# InkTime_Schematic.net
KiCad netlist of a schematic drawn in EAGLE
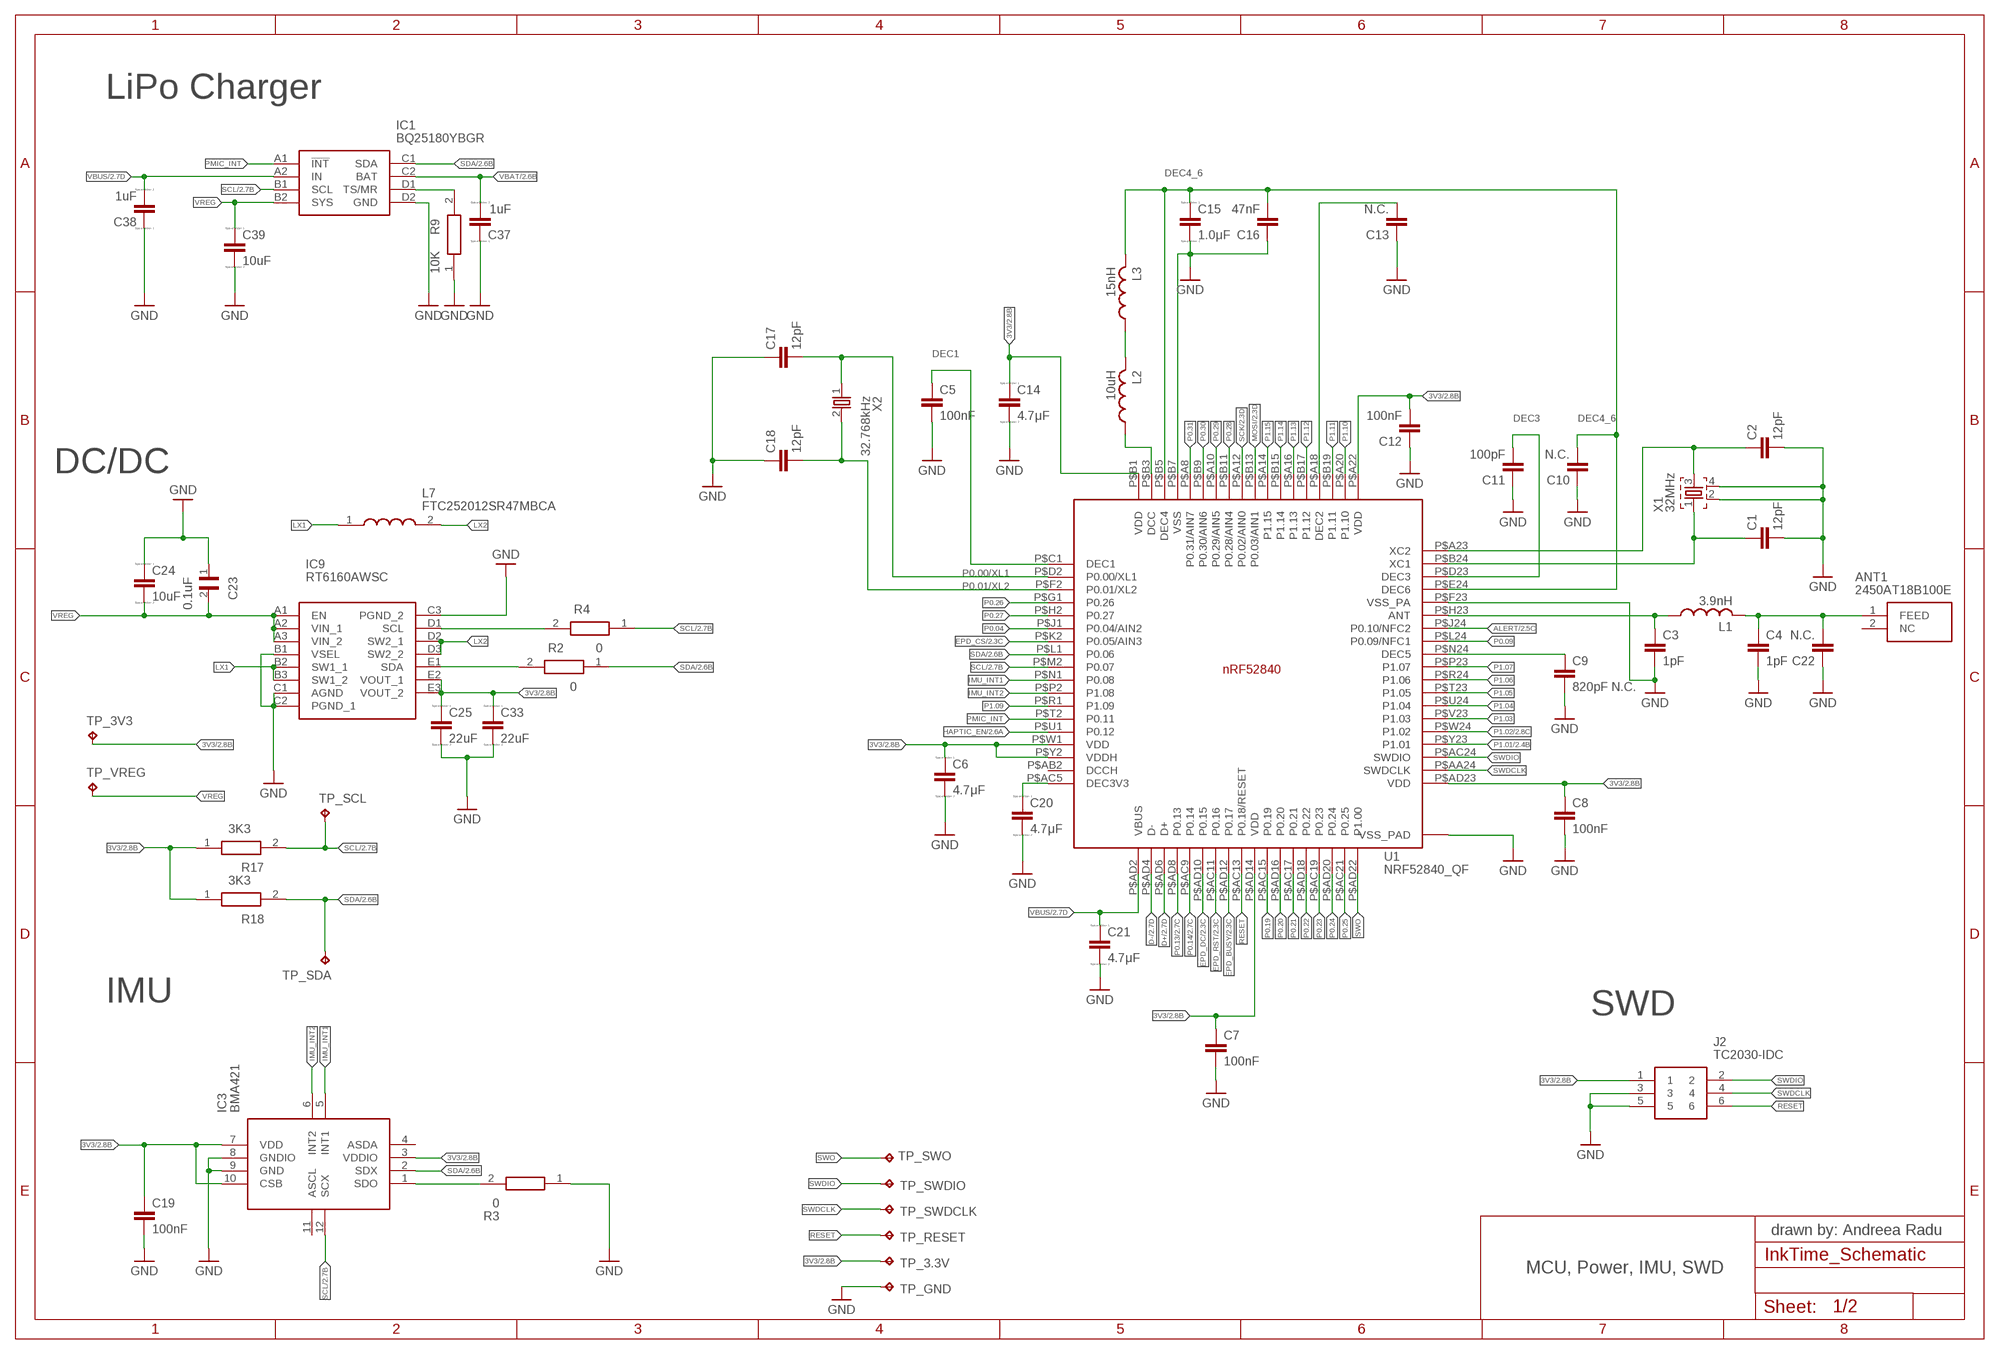
[diagram p0: schematic, sheet 1]
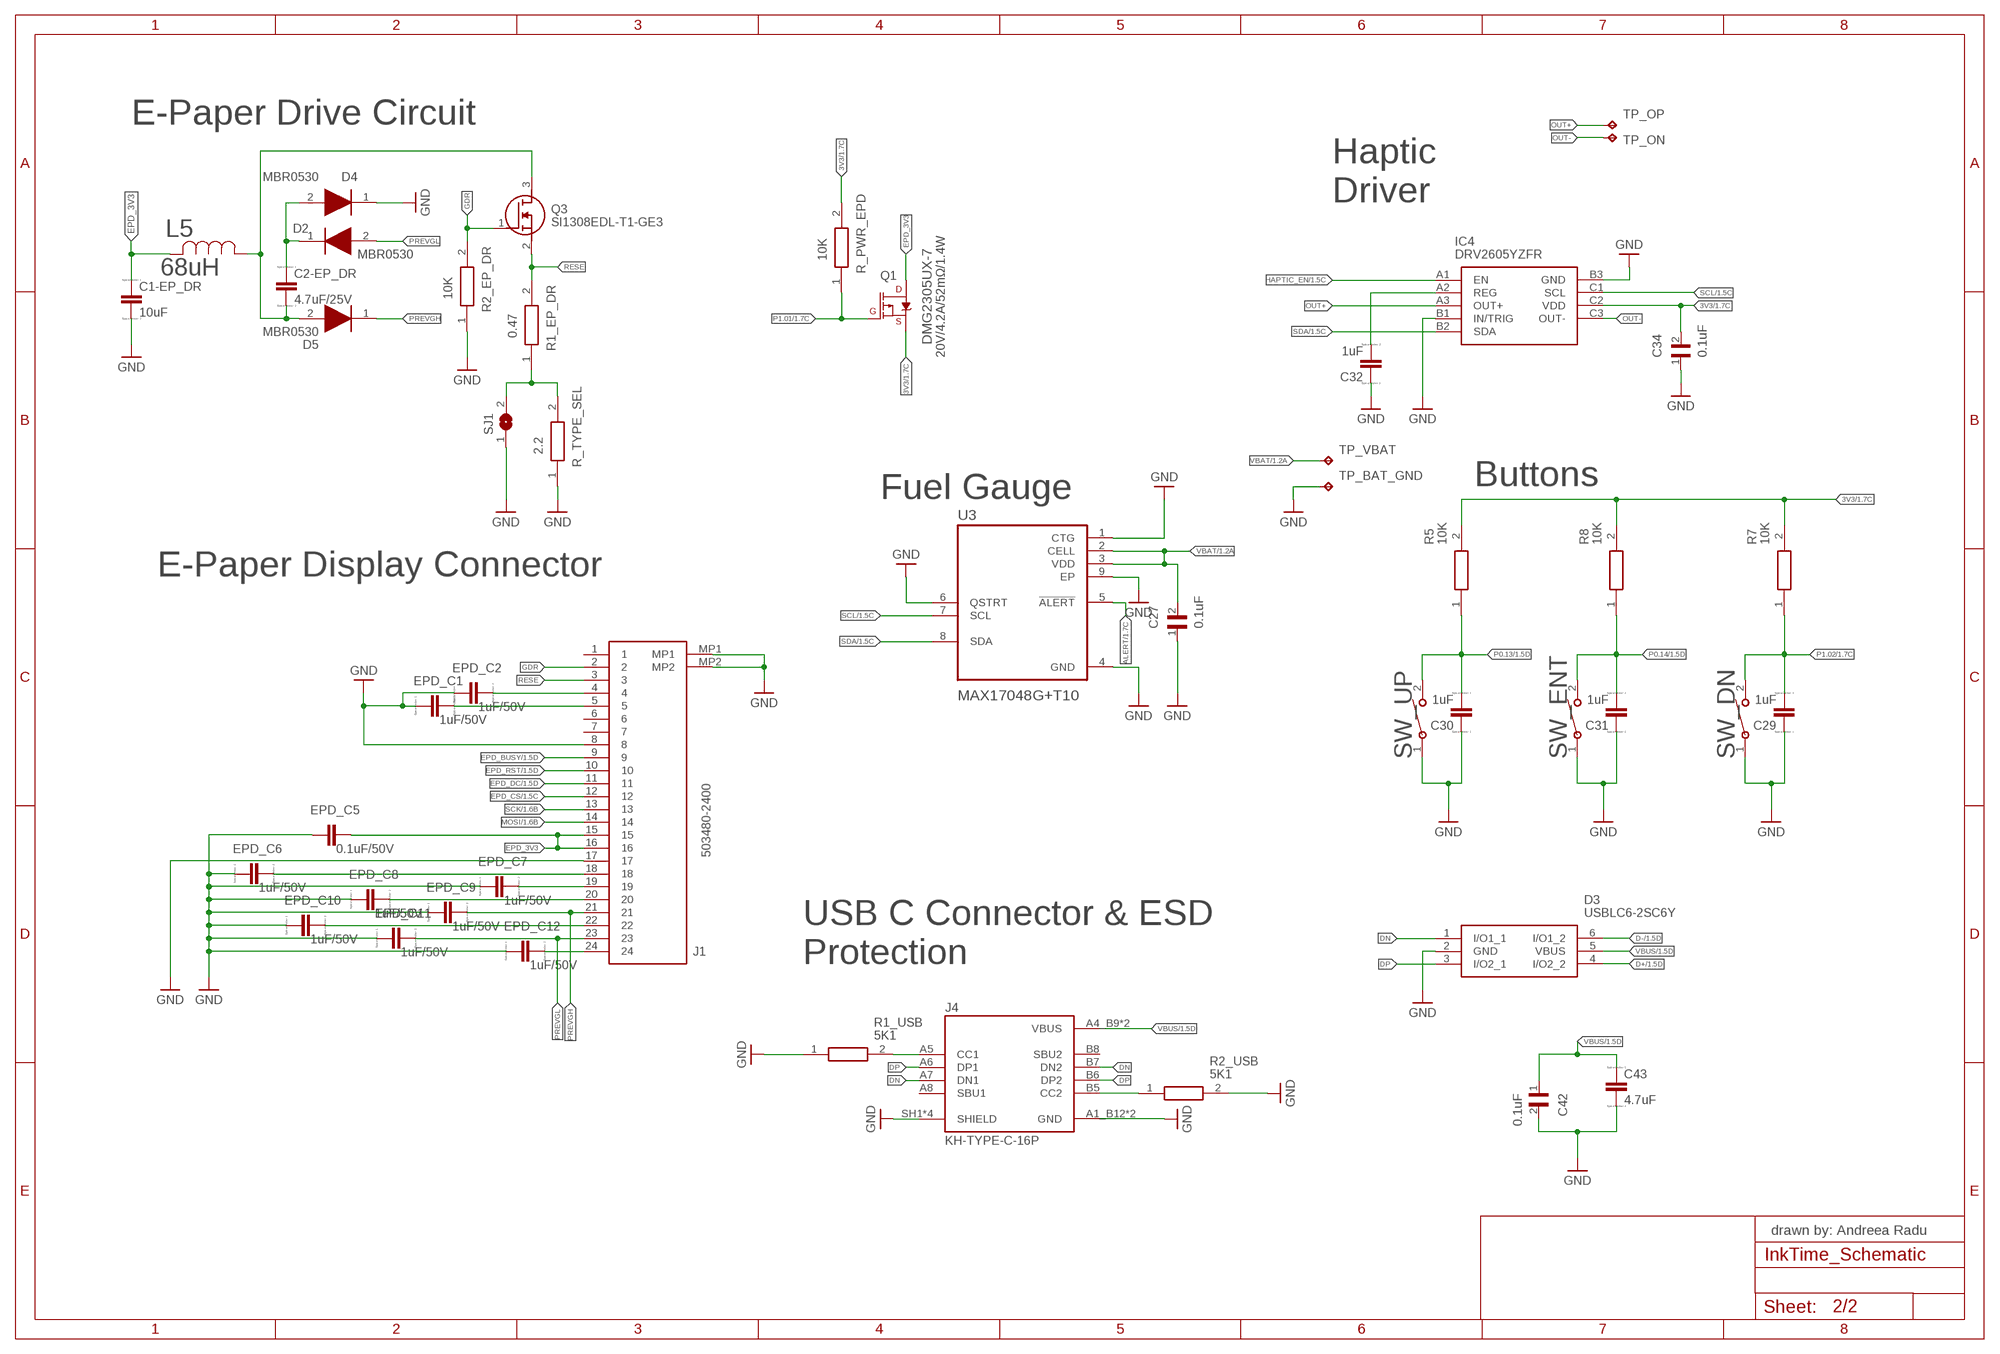
[diagram p1: schematic, sheet 2]

(export (version "E")
  (design (tool "Eeschema 10.0.6"))
  (components
    (comp (ref "ANT1")
      (value "2450AT18B100E")
      (footprint "eagle-import:2450AT18B100E_ANTC3216X140N")
      (fields (field (name "MOUSER_PART_NUMBER") "609-2450AT18B100E"))
      (libsource (lib "eagle-import") (part "2450AT18B100E_2450AT18B100E"))
    )
    (comp (ref "C1")
      (value "12pF")
      (footprint "eagle-import:NORDIC_NRF_3_RESC0201_L")
      (libsource (lib "eagle-import") (part "NORDIC_NRF_3_CAPACITOR_0201_L"))
    )
    (comp (ref "C2")
      (value "12pF")
      (footprint "eagle-import:NORDIC_NRF_3_RESC0201_L")
      (libsource (lib "eagle-import") (part "NORDIC_NRF_3_CAPACITOR_0201_L"))
    )
    (comp (ref "C3")
      (value "1pF")
      (footprint "eagle-import:NORDIC_NRF_3_RESC0201_L")
      (libsource (lib "eagle-import") (part "NORDIC_NRF_3_CAPACITOR_0201_L"))
    )
    (comp (ref "C4")
      (value "1pF")
      (footprint "eagle-import:NORDIC_NRF_3_RESC0201_L")
      (libsource (lib "eagle-import") (part "NORDIC_NRF_3_CAPACITOR_0201_L"))
    )
    (comp (ref "C5")
      (value "100nF")
      (footprint "eagle-import:NORDIC_NRF_3_RESC0201_L")
      (libsource (lib "eagle-import") (part "NORDIC_NRF_3_CAPACITOR_0201_L"))
    )
    (comp (ref "C6")
      (value "4.7μF")
      (footprint "eagle-import:ESP32_C6_LIBRARY_1_ESP32_WROVER_EAGLE-LTSPICE_C0402")
      (libsource (lib "eagle-import") (part "ESP32_C6_LIBRARY_1_ESP32_WROVER_EAGLE-LTSPICE_CC0402"))
    )
    (comp (ref "C7")
      (value "100nF")
      (footprint "eagle-import:NORDIC_NRF_3_RESC0201_L")
      (libsource (lib "eagle-import") (part "NORDIC_NRF_3_CAPACITOR_0201_L"))
    )
    (comp (ref "C8")
      (value "100nF")
      (footprint "eagle-import:NORDIC_NRF_3_RESC0201_L")
      (libsource (lib "eagle-import") (part "NORDIC_NRF_3_CAPACITOR_0201_L"))
    )
    (comp (ref "C9")
      (value "820pF N.C.")
      (footprint "eagle-import:NORDIC_NRF_3_RESC0201_L")
      (libsource (lib "eagle-import") (part "NORDIC_NRF_3_CAPACITOR_0201_L"))
    )
    (comp (ref "C10")
      (value "N.C.")
      (footprint "eagle-import:NORDIC_NRF_3_RESC0201_L")
      (libsource (lib "eagle-import") (part "NORDIC_NRF_3_CAPACITOR_0201_L"))
    )
    (comp (ref "C11")
      (value "100pF")
      (footprint "eagle-import:NORDIC_NRF_3_RESC0201_L")
      (libsource (lib "eagle-import") (part "NORDIC_NRF_3_CAPACITOR_0201_L"))
    )
    (comp (ref "C12")
      (value "100nF")
      (footprint "eagle-import:NORDIC_NRF_3_RESC0201_L")
      (libsource (lib "eagle-import") (part "NORDIC_NRF_3_CAPACITOR_0201_L"))
    )
    (comp (ref "C13")
      (value "N.C.")
      (footprint "eagle-import:NORDIC_NRF_3_RESC0201_L")
      (libsource (lib "eagle-import") (part "NORDIC_NRF_3_CAPACITOR_0201_L"))
    )
    (comp (ref "C14")
      (value "4.7μF")
      (footprint "eagle-import:ESP32_C6_LIBRARY_1_ESP32_WROVER_EAGLE-LTSPICE_C0402")
      (libsource (lib "eagle-import") (part "ESP32_C6_LIBRARY_1_ESP32_WROVER_EAGLE-LTSPICE_CC0402"))
    )
    (comp (ref "C15")
      (value "1.0μF")
      (footprint "eagle-import:ESP32_C6_LIBRARY_1_ESP32_WROVER_EAGLE-LTSPICE_C0402")
      (libsource (lib "eagle-import") (part "ESP32_C6_LIBRARY_1_ESP32_WROVER_EAGLE-LTSPICE_CC0402"))
    )
    (comp (ref "C16")
      (value "47nF")
      (footprint "eagle-import:NORDIC_NRF_3_RESC0201_L")
      (libsource (lib "eagle-import") (part "NORDIC_NRF_3_CAPACITOR_0201_L"))
    )
    (comp (ref "C17")
      (value "12pF")
      (footprint "eagle-import:NORDIC_NRF_3_RESC0201_L")
      (libsource (lib "eagle-import") (part "NORDIC_NRF_3_CAPACITOR_0201_L"))
    )
    (comp (ref "C18")
      (value "12pF")
      (footprint "eagle-import:NORDIC_NRF_3_RESC0201_L")
      (libsource (lib "eagle-import") (part "NORDIC_NRF_3_CAPACITOR_0201_L"))
    )
    (comp (ref "C19")
      (value "100nF")
      (footprint "eagle-import:NORDIC_NRF_3_RESC0201_L")
      (libsource (lib "eagle-import") (part "NORDIC_NRF_3_CAPACITOR_0201_L"))
    )
    (comp (ref "C20")
      (value "4.7μF")
      (footprint "eagle-import:ESP32_C6_LIBRARY_1_ESP32_WROVER_EAGLE-LTSPICE_C0402")
      (libsource (lib "eagle-import") (part "ESP32_C6_LIBRARY_1_ESP32_WROVER_EAGLE-LTSPICE_CC0402"))
    )
    (comp (ref "C21")
      (value "4.7μF")
      (footprint "eagle-import:ESP32_C6_LIBRARY_1_ESP32_WROVER_EAGLE-LTSPICE_C0402")
      (libsource (lib "eagle-import") (part "ESP32_C6_LIBRARY_1_ESP32_WROVER_EAGLE-LTSPICE_CC0402"))
    )
    (comp (ref "C22")
      (value "N.C.")
      (footprint "eagle-import:NORDIC_NRF_3_RESC0201_L")
      (libsource (lib "eagle-import") (part "NORDIC_NRF_3_CAPACITOR_0201_L"))
    )
    (comp (ref "C23")
      (value "0.1uF")
      (footprint "eagle-import:GRM011R60J152KE01L_2_CAPC0201X13N")
      (fields (field (name "MF") "Murata") (field (name "MP") "GRM011R60J152KE01L"))
      (libsource (lib "eagle-import") (part "GRM011R60J152KE01L_2_GRM011R60J152KE01L"))
    )
    (comp (ref "C24")
      (value "10uF")
      (footprint "eagle-import:ESP32_C6_LIBRARY_1_ESP32_WROVER_EAGLE-LTSPICE_C0402")
      (libsource (lib "eagle-import") (part "ESP32_C6_LIBRARY_1_ESP32_WROVER_EAGLE-LTSPICE_CC0402"))
    )
    (comp (ref "C25")
      (value "22uF")
      (footprint "eagle-import:ESP32_C6_LIBRARY_1_ESP32_WROVER_EAGLE-LTSPICE_C0402")
      (libsource (lib "eagle-import") (part "ESP32_C6_LIBRARY_1_ESP32_WROVER_EAGLE-LTSPICE_CC0402"))
    )
    (comp (ref "C33")
      (value "22uF")
      (footprint "eagle-import:ESP32_C6_LIBRARY_1_ESP32_WROVER_EAGLE-LTSPICE_C0402")
      (libsource (lib "eagle-import") (part "ESP32_C6_LIBRARY_1_ESP32_WROVER_EAGLE-LTSPICE_CC0402"))
    )
    (comp (ref "C37")
      (value "1uF")
      (footprint "eagle-import:ESP32_C6_LIBRARY_1_ESP32_WROVER_EAGLE-LTSPICE_C0402")
      (libsource (lib "eagle-import") (part "ESP32_C6_LIBRARY_1_ESP32_WROVER_EAGLE-LTSPICE_CC0402"))
    )
    (comp (ref "C38")
      (value "1uF")
      (footprint "eagle-import:ESP32_C6_LIBRARY_1_ESP32_WROVER_EAGLE-LTSPICE_C0402")
      (libsource (lib "eagle-import") (part "ESP32_C6_LIBRARY_1_ESP32_WROVER_EAGLE-LTSPICE_CC0402"))
    )
    (comp (ref "C39")
      (value "10uF")
      (footprint "eagle-import:ESP32_C6_LIBRARY_1_ESP32_WROVER_EAGLE-LTSPICE_C0402")
      (libsource (lib "eagle-import") (part "ESP32_C6_LIBRARY_1_ESP32_WROVER_EAGLE-LTSPICE_CC0402"))
    )
    (comp (ref "IC1")
      (value "BQ25180YBGR")
      (footprint "eagle-import:BQ25180YBGR_BGA8C40P2X4_100X155X50")
      (fields (field (name "MOUSER_PART_NUMBER") "595-BQ25180YBGR"))
      (libsource (lib "eagle-import") (part "BQ25180YBGR_BQ25180YBGR"))
    )
    (comp (ref "IC3")
      (value "BMA421")
      (footprint "eagle-import:BMA423_BMA423")
      (fields (field (name "ARROW_PART_NUMBER") "BMA423") (field (name "MOUSER_PART_NUMBER") "262-BMA423"))
      (libsource (lib "eagle-import") (part "BMA423_BMA423"))
    )
    (comp (ref "IC9")
      (value "RT6160AWSC")
      (footprint "eagle-import:RT6160AWSC_BGA15C40P3X5_140X230X60")
      (fields (field (name "MOUSER_PART_NUMBER") "835-RT6160AWSC"))
      (libsource (lib "eagle-import") (part "RT6160AWSC_RT6160AWSC"))
    )
    (comp (ref "J2")
      (value "TC2030-IDC")
      (footprint "eagle-import:TC2030-IDC_TC2030IDC")
      (libsource (lib "eagle-import") (part "TC2030-IDC_TC2030-IDC"))
    )
    (comp (ref "L1")
      (value "3.9nH")
      (footprint "eagle-import:NORDIC_NRF_2_RESC0402_L")
      (libsource (lib "eagle-import") (part "NORDIC_NRF_2_INDUCTOR_0402_L"))
    )
    (comp (ref "L2")
      (value "10uH")
      (footprint "eagle-import:NORDIC_NRF_2_RESC0402_L")
      (libsource (lib "eagle-import") (part "NORDIC_NRF_2_INDUCTOR_0402_L"))
    )
    (comp (ref "L3")
      (value "15nH")
      (footprint "eagle-import:NORDIC_NRF_2_RESC0402_L")
      (libsource (lib "eagle-import") (part "NORDIC_NRF_2_INDUCTOR_0402_L"))
    )
    (comp (ref "L7")
      (value "FTC252012SR47MBCA")
      (footprint "eagle-import:MLP2016SR47MT0S1_INDC2016X100N")
      (libsource (lib "eagle-import") (part "MLP2016SR47MT0S1_FTC252012SR47MBCA"))
    )
    (comp (ref "R2")
      (value "0")
      (footprint "eagle-import:CPF0201D7K68C1_0201")
      (libsource (lib "eagle-import") (part "CPF0201D7K68C1_CPF0201D7K68C1"))
    )
    (comp (ref "R3")
      (value "0")
      (footprint "eagle-import:CPF0201D7K68C1_0201")
      (libsource (lib "eagle-import") (part "CPF0201D7K68C1_CPF0201D7K68C1"))
    )
    (comp (ref "R4")
      (value "0")
      (footprint "eagle-import:CPF0201D7K68C1_0201")
      (libsource (lib "eagle-import") (part "CPF0201D7K68C1_CPF0201D7K68C1"))
    )
    (comp (ref "R9")
      (value "10K")
      (footprint "eagle-import:CPF0201D7K68C1_0201")
      (libsource (lib "eagle-import") (part "CPF0201D7K68C1_CPF0201D7K68C1"))
    )
    (comp (ref "R17")
      (value "3K3")
      (footprint "eagle-import:CPF0201D7K68C1_0201")
      (libsource (lib "eagle-import") (part "CPF0201D7K68C1_CPF0201D7K68C1"))
    )
    (comp (ref "R18")
      (value "3K3")
      (footprint "eagle-import:CPF0201D7K68C1_0201")
      (libsource (lib "eagle-import") (part "CPF0201D7K68C1_CPF0201D7K68C1"))
    )
    (comp (ref "TP_3.3V")
      (value "HECTOR_WATCH_1_TPTP20R")
      (footprint "eagle-import:HECTOR_WATCH_1_TP20R")
      (libsource (lib "eagle-import") (part "HECTOR_WATCH_1_TPTP20R"))
    )
    (comp (ref "TP_3V3")
      (value "HECTOR_WATCH_1_TPTP20R")
      (footprint "eagle-import:HECTOR_WATCH_1_TP20R")
      (libsource (lib "eagle-import") (part "HECTOR_WATCH_1_TPTP20R"))
    )
    (comp (ref "TP_GND")
      (value "HECTOR_WATCH_1_TPTP20R")
      (footprint "eagle-import:HECTOR_WATCH_1_TP20R")
      (libsource (lib "eagle-import") (part "HECTOR_WATCH_1_TPTP20R"))
    )
    (comp (ref "TP_RESET")
      (value "HECTOR_WATCH_1_TPTP20R")
      (footprint "eagle-import:HECTOR_WATCH_1_TP20R")
      (libsource (lib "eagle-import") (part "HECTOR_WATCH_1_TPTP20R"))
    )
    (comp (ref "TP_SCL")
      (value "HECTOR_WATCH_1_TPTP20R")
      (footprint "eagle-import:HECTOR_WATCH_1_TP20R")
      (libsource (lib "eagle-import") (part "HECTOR_WATCH_1_TPTP20R"))
    )
    (comp (ref "TP_SDA")
      (value "HECTOR_WATCH_1_TPTP20R")
      (footprint "eagle-import:HECTOR_WATCH_1_TP20R")
      (libsource (lib "eagle-import") (part "HECTOR_WATCH_1_TPTP20R"))
    )
    (comp (ref "TP_SWDCLK")
      (value "HECTOR_WATCH_1_TPTP20R")
      (footprint "eagle-import:HECTOR_WATCH_1_TP20R")
      (libsource (lib "eagle-import") (part "HECTOR_WATCH_1_TPTP20R"))
    )
    (comp (ref "TP_SWDIO")
      (value "HECTOR_WATCH_1_TPTP20R")
      (footprint "eagle-import:HECTOR_WATCH_1_TP20R")
      (libsource (lib "eagle-import") (part "HECTOR_WATCH_1_TPTP20R"))
    )
    (comp (ref "TP_SWO")
      (value "HECTOR_WATCH_1_TPTP20R")
      (footprint "eagle-import:HECTOR_WATCH_1_TP20R")
      (libsource (lib "eagle-import") (part "HECTOR_WATCH_1_TPTP20R"))
    )
    (comp (ref "TP_VREG")
      (value "HECTOR_WATCH_1_TPTP20R")
      (footprint "eagle-import:HECTOR_WATCH_1_TP20R")
      (libsource (lib "eagle-import") (part "HECTOR_WATCH_1_TPTP20R"))
    )
    (comp (ref "U1")
      (value "NRF52840_QF")
      (footprint "eagle-import:NORDIC_NRF_4_AQFN50P700X700X85_HS-74N")
      (libsource (lib "eagle-import") (part "NORDIC_NRF_4_NRF52840_QF"))
    )
    (comp (ref "X1")
      (value "32MHz")
      (footprint "eagle-import:NORDIC_NRF_BT-XTAL_2016_N")
      (libsource (lib "eagle-import") (part "NORDIC_NRF_XTAL_32MHZ"))
    )
    (comp (ref "X2")
      (value "32.768kHz")
      (footprint "eagle-import:NORDIC_NRF_1_XTAL_3215_N")
      (libsource (lib "eagle-import") (part "NORDIC_NRF_1_XTAL_32KHZ"))
    )
    (comp (ref "C1-EP_DR")
      (value "10uF")
      (footprint "eagle-import:ESP32_C6_LIBRARY_1_ESP32_WROVER_EAGLE-LTSPICE_C0402")
      (libsource (lib "eagle-import") (part "ESP32_C6_LIBRARY_1_ESP32_WROVER_EAGLE-LTSPICE_CC0402"))
    )
    (comp (ref "C2-EP_DR")
      (value "4.7uF/25V")
      (footprint "eagle-import:ESP32_C6_LIBRARY_1_ESP32_WROVER_EAGLE-LTSPICE_C0402")
      (libsource (lib "eagle-import") (part "ESP32_C6_LIBRARY_1_ESP32_WROVER_EAGLE-LTSPICE_CC0402"))
    )
    (comp (ref "C27")
      (value "0.1uF")
      (footprint "eagle-import:GRM011R60J152KE01L_2_CAPC0201X13N")
      (fields (field (name "MF") "Murata") (field (name "MP") "GRM011R60J152KE01L"))
      (libsource (lib "eagle-import") (part "GRM011R60J152KE01L_2_GRM011R60J152KE01L"))
    )
    (comp (ref "C29")
      (value "1uF")
      (footprint "eagle-import:ESP32_C6_LIBRARY_1_ESP32_WROVER_EAGLE-LTSPICE_C0402")
      (libsource (lib "eagle-import") (part "ESP32_C6_LIBRARY_1_ESP32_WROVER_EAGLE-LTSPICE_CC0402"))
    )
    (comp (ref "C30")
      (value "1uF")
      (footprint "eagle-import:ESP32_C6_LIBRARY_1_ESP32_WROVER_EAGLE-LTSPICE_C0402")
      (libsource (lib "eagle-import") (part "ESP32_C6_LIBRARY_1_ESP32_WROVER_EAGLE-LTSPICE_CC0402"))
    )
    (comp (ref "C31")
      (value "1uF")
      (footprint "eagle-import:ESP32_C6_LIBRARY_1_ESP32_WROVER_EAGLE-LTSPICE_C0402")
      (libsource (lib "eagle-import") (part "ESP32_C6_LIBRARY_1_ESP32_WROVER_EAGLE-LTSPICE_CC0402"))
    )
    (comp (ref "C32")
      (value "1uF")
      (footprint "eagle-import:ESP32_C6_LIBRARY_1_ESP32_WROVER_EAGLE-LTSPICE_C0402")
      (libsource (lib "eagle-import") (part "ESP32_C6_LIBRARY_1_ESP32_WROVER_EAGLE-LTSPICE_CC0402"))
    )
    (comp (ref "C34")
      (value "0.1uF")
      (footprint "eagle-import:GRM011R60J152KE01L_2_CAPC0201X13N")
      (fields (field (name "MF") "Murata") (field (name "MP") "GRM011R60J152KE01L"))
      (libsource (lib "eagle-import") (part "GRM011R60J152KE01L_2_GRM011R60J152KE01L"))
    )
    (comp (ref "C42")
      (value "0.1uF")
      (footprint "eagle-import:GRM011R60J152KE01L_2_CAPC0201X13N")
      (fields (field (name "MF") "Murata") (field (name "MP") "GRM011R60J152KE01L"))
      (libsource (lib "eagle-import") (part "GRM011R60J152KE01L_2_GRM011R60J152KE01L"))
    )
    (comp (ref "C43")
      (value "4.7uF")
      (footprint "eagle-import:ESP32_C6_LIBRARY_1_ESP32_WROVER_EAGLE-LTSPICE_C0402")
      (libsource (lib "eagle-import") (part "ESP32_C6_LIBRARY_1_ESP32_WROVER_EAGLE-LTSPICE_CC0402"))
    )
    (comp (ref "D2")
      (value "MBR0530")
      (footprint "eagle-import:ESP32_C6_LIBRARY_5_SOD3716X135N")
      (fields (field (name "MF") "ON Semiconductor"))
      (libsource (lib "eagle-import") (part "ESP32_C6_LIBRARY_5_MBR0530"))
    )
    (comp (ref "D3")
      (value "USBLC6-2SC6Y")
      (footprint "eagle-import:ESP32_C6_LIBRARY_3_SOT95P280X145-6N")
      (fields (field (name "MF") "STMicroelectronics"))
      (libsource (lib "eagle-import") (part "ESP32_C6_LIBRARY_3_USBLC6-2SC6Y"))
    )
    (comp (ref "D4")
      (value "MBR0530")
      (footprint "eagle-import:ESP32_C6_LIBRARY_5_SOD3716X135N")
      (fields (field (name "MF") "ON Semiconductor"))
      (libsource (lib "eagle-import") (part "ESP32_C6_LIBRARY_5_MBR0530"))
    )
    (comp (ref "D5")
      (value "MBR0530")
      (footprint "eagle-import:ESP32_C6_LIBRARY_5_SOD3716X135N")
      (fields (field (name "MF") "ON Semiconductor"))
      (libsource (lib "eagle-import") (part "ESP32_C6_LIBRARY_5_MBR0530"))
    )
    (comp (ref "EPD_C1")
      (value "1uF/50V")
      (footprint "eagle-import:ESP32_C6_LIBRARY_1_ESP32_WROVER_EAGLE-LTSPICE_C0402")
      (libsource (lib "eagle-import") (part "ESP32_C6_LIBRARY_1_ESP32_WROVER_EAGLE-LTSPICE_CC0402"))
    )
    (comp (ref "EPD_C2")
      (value "1uF/50V")
      (footprint "eagle-import:ESP32_C6_LIBRARY_1_ESP32_WROVER_EAGLE-LTSPICE_C0402")
      (libsource (lib "eagle-import") (part "ESP32_C6_LIBRARY_1_ESP32_WROVER_EAGLE-LTSPICE_CC0402"))
    )
    (comp (ref "EPD_C5")
      (value "0.1uF/50V")
      (footprint "eagle-import:NORDIC_NRF_3_RESC0201_L")
      (libsource (lib "eagle-import") (part "NORDIC_NRF_3_CAPACITOR_0201_L"))
    )
    (comp (ref "EPD_C6")
      (value "1uF/50V")
      (footprint "eagle-import:ESP32_C6_LIBRARY_1_ESP32_WROVER_EAGLE-LTSPICE_C0402")
      (libsource (lib "eagle-import") (part "ESP32_C6_LIBRARY_1_ESP32_WROVER_EAGLE-LTSPICE_CC0402"))
    )
    (comp (ref "EPD_C7")
      (value "1uF/50V")
      (footprint "eagle-import:ESP32_C6_LIBRARY_1_ESP32_WROVER_EAGLE-LTSPICE_C0402")
      (libsource (lib "eagle-import") (part "ESP32_C6_LIBRARY_1_ESP32_WROVER_EAGLE-LTSPICE_CC0402"))
    )
    (comp (ref "EPD_C8")
      (value "1uF/50V")
      (footprint "eagle-import:ESP32_C6_LIBRARY_1_ESP32_WROVER_EAGLE-LTSPICE_C0402")
      (libsource (lib "eagle-import") (part "ESP32_C6_LIBRARY_1_ESP32_WROVER_EAGLE-LTSPICE_CC0402"))
    )
    (comp (ref "EPD_C9")
      (value "1uF/50V")
      (footprint "eagle-import:ESP32_C6_LIBRARY_1_ESP32_WROVER_EAGLE-LTSPICE_C0402")
      (libsource (lib "eagle-import") (part "ESP32_C6_LIBRARY_1_ESP32_WROVER_EAGLE-LTSPICE_CC0402"))
    )
    (comp (ref "EPD_C10")
      (value "1uF/50V")
      (footprint "eagle-import:ESP32_C6_LIBRARY_1_ESP32_WROVER_EAGLE-LTSPICE_C0402")
      (libsource (lib "eagle-import") (part "ESP32_C6_LIBRARY_1_ESP32_WROVER_EAGLE-LTSPICE_CC0402"))
    )
    (comp (ref "EPD_C11")
      (value "1uF/50V")
      (footprint "eagle-import:ESP32_C6_LIBRARY_1_ESP32_WROVER_EAGLE-LTSPICE_C0402")
      (libsource (lib "eagle-import") (part "ESP32_C6_LIBRARY_1_ESP32_WROVER_EAGLE-LTSPICE_CC0402"))
    )
    (comp (ref "EPD_C12")
      (value "1uF/50V")
      (footprint "eagle-import:ESP32_C6_LIBRARY_1_ESP32_WROVER_EAGLE-LTSPICE_C0402")
      (libsource (lib "eagle-import") (part "ESP32_C6_LIBRARY_1_ESP32_WROVER_EAGLE-LTSPICE_CC0402"))
    )
    (comp (ref "IC4")
      (value "DRV2605YZFR")
      (footprint "eagle-import:DRV2605YZFR_BGA9C50P3X3_144X144X62")
      (libsource (lib "eagle-import") (part "DRV2605YZFR_DRV2605YZFR"))
    )
    (comp (ref "J1")
      (value "503480-2400")
      (footprint "eagle-import:503480-2400_5034802400")
      (fields (field (name "MOUSER_PART_NUMBER") "538-503480-2400"))
      (libsource (lib "eagle-import") (part "503480-2400_503480-2400"))
    )
    (comp (ref "J4")
      (value "KH-TYPE-C-16P")
      (footprint "eagle-import:KH-TYPE-C-16P_KINGHELM_KH-TYPE-C-16P")
      (fields (field (name "MF") "kinghelm"))
      (libsource (lib "eagle-import") (part "KH-TYPE-C-16P_KH-TYPE-C-16P"))
    )
    (comp (ref "L5")
      (value "68uH")
      (footprint "eagle-import:ESP32_C6_LIBRARY_2_IND_4828-WE-TPC_WRE")
      (fields
        (field (name "MANUFACTURER_PART_NUMBER") "744043680")
        (field (name "COPYRIGHT") "Copyright (C) 2024 Ultra Librarian. All rights reserved.")
      )
      (libsource (lib "eagle-import") (part "ESP32_C6_LIBRARY_2_744043680IND_4828-WE-TPC_WRE"))
    )
    (comp (ref "Q1")
      (value "20V/4.2A/52mΩ/1.4W")
      (footprint "eagle-import:ESP32_C6_LIBRARY_4_ESP32_C6_LIBRARY_4_ESP32_C6_LIBRARY_4_ESP32_C6_LIBRARY_4_ESP32_WROVER_SPARKFUN-DISCRETESEMI_SOT23-3")
      (libsource (lib "eagle-import") (part "ESP32_C6_LIBRARY_4_ESP32_WROVER_SPARKFUN-DISCRETESEMI_MOSFET_PCH-DMG2305UX-7"))
    )
    (comp (ref "Q3")
      (value "SI1308EDL-T1-GE3")
      (footprint "eagle-import:ESP32_C6_LIBRARY_6_SOT65P210X110-3N")
      (fields (field (name "MF") "Vishay Siliconix"))
      (libsource (lib "eagle-import") (part "ESP32_C6_LIBRARY_6_SI1308EDL-T1-GE3"))
    )
    (comp (ref "R1_EP_DR")
      (value "0.47")
      (footprint "eagle-import:CPF0201D7K68C1_0201")
      (libsource (lib "eagle-import") (part "CPF0201D7K68C1_CPF0201D7K68C1"))
    )
    (comp (ref "R1_USB")
      (value "5K1")
      (footprint "eagle-import:ERA-1AEB3401C_0201")
      (libsource (lib "eagle-import") (part "ERA-1AEB3401C_CPF0201D7K68C1"))
    )
    (comp (ref "R2_EP_DR")
      (value "10K")
      (footprint "eagle-import:CPF0201D7K68C1_0201")
      (libsource (lib "eagle-import") (part "CPF0201D7K68C1_CPF0201D7K68C1"))
    )
    (comp (ref "R2_USB")
      (value "5K1")
      (footprint "eagle-import:ERA-1AEB3401C_0201")
      (libsource (lib "eagle-import") (part "ERA-1AEB3401C_CPF0201D7K68C1"))
    )
    (comp (ref "R5")
      (value "10K")
      (footprint "eagle-import:ERA-1AEB3401C_0201")
      (libsource (lib "eagle-import") (part "ERA-1AEB3401C_CPF0201D7K68C1"))
    )
    (comp (ref "R7")
      (value "10K")
      (footprint "eagle-import:ERA-1AEB3401C_0201")
      (libsource (lib "eagle-import") (part "ERA-1AEB3401C_CPF0201D7K68C1"))
    )
    (comp (ref "R8")
      (value "10K")
      (footprint "eagle-import:ERA-1AEB3401C_0201")
      (libsource (lib "eagle-import") (part "ERA-1AEB3401C_CPF0201D7K68C1"))
    )
    (comp (ref "R_PWR_EPD")
      (value "10K")
      (footprint "eagle-import:CPF0201D7K68C1_0201")
      (libsource (lib "eagle-import") (part "CPF0201D7K68C1_CPF0201D7K68C1"))
    )
    (comp (ref "R_TYPE_SEL")
      (value "2.2")
      (footprint "eagle-import:CPF0201D7K68C1_0201")
      (libsource (lib "eagle-import") (part "CPF0201D7K68C1_CPF0201D7K68C1"))
    )
    (comp (ref "SJ1")
      (value "ESP32_C6_LIBRARY_7_JUMPER_SJ")
      (footprint "eagle-import:ESP32_C6_LIBRARY_7_JUMPER_SJ")
      (libsource (lib "eagle-import") (part "ESP32_C6_LIBRARY_7_JUMPER_SJ"))
    )
    (comp (ref "SW_DN")
      (value "2025-10-22_07-23-44_LIBRARY_EVP-AKE31ASW_EVP-AKE31A_PAN")
      (footprint "eagle-import:2025-10-22_07-23-44_LIBRARY_SW_EVP-AKE31A_PAN")
      (fields
        (field (name "MANUFACTURER_PART_NUMBER") "EVP-AKE31A")
        (field (name "COPYRIGHT") "Copyright (C) 2025 Ultra Librarian. All rights reserved.")
      )
      (libsource (lib "eagle-import") (part "2025-10-22_07-23-44_LIBRARY_EVP-AKE31ASW_EVP-AKE31A_PAN"))
    )
    (comp (ref "SW_ENT")
      (value "2025-10-22_07-23-44_LIBRARY_EVP-AKE31ASW_EVP-AKE31A_PAN")
      (footprint "eagle-import:2025-10-22_07-23-44_LIBRARY_SW_EVP-AKE31A_PAN")
      (fields
        (field (name "MANUFACTURER_PART_NUMBER") "EVP-AKE31A")
        (field (name "COPYRIGHT") "Copyright (C) 2025 Ultra Librarian. All rights reserved.")
      )
      (libsource (lib "eagle-import") (part "2025-10-22_07-23-44_LIBRARY_EVP-AKE31ASW_EVP-AKE31A_PAN"))
    )
    (comp (ref "SW_UP")
      (value "2025-10-22_07-23-44_LIBRARY_EVP-AKE31ASW_EVP-AKE31A_PAN")
      (footprint "eagle-import:2025-10-22_07-23-44_LIBRARY_SW_EVP-AKE31A_PAN")
      (fields
        (field (name "MANUFACTURER_PART_NUMBER") "EVP-AKE31A")
        (field (name "COPYRIGHT") "Copyright (C) 2025 Ultra Librarian. All rights reserved.")
      )
      (libsource (lib "eagle-import") (part "2025-10-22_07-23-44_LIBRARY_EVP-AKE31ASW_EVP-AKE31A_PAN"))
    )
    (comp (ref "TP_BAT_GND")
      (value "HECTOR_WATCH_1_TPTP20R")
      (footprint "eagle-import:HECTOR_WATCH_1_TP20R")
      (libsource (lib "eagle-import") (part "HECTOR_WATCH_1_TPTP20R"))
    )
    (comp (ref "TP_ON")
      (value "HECTOR_WATCH_1_TPTP20R")
      (footprint "eagle-import:HECTOR_WATCH_1_TP20R")
      (libsource (lib "eagle-import") (part "HECTOR_WATCH_1_TPTP20R"))
    )
    (comp (ref "TP_OP")
      (value "HECTOR_WATCH_1_TPTP20R")
      (footprint "eagle-import:HECTOR_WATCH_1_TP20R")
      (libsource (lib "eagle-import") (part "HECTOR_WATCH_1_TPTP20R"))
    )
    (comp (ref "TP_VBAT")
      (value "HECTOR_WATCH_1_TPTP20R")
      (footprint "eagle-import:HECTOR_WATCH_1_TP20R")
      (libsource (lib "eagle-import") (part "HECTOR_WATCH_1_TPTP20R"))
    )
    (comp (ref "U3")
      (value "MAX17048G+T10")
      (footprint "eagle-import:ESP32_C6_LIBRARY_SON50P200X200X80-9N")
      (fields (field (name "MF") "Analog Devices"))
      (libsource (lib "eagle-import") (part "ESP32_C6_LIBRARY_MAX17048G+T10"))
    )
  )
  (nets
    (net (code "1") (name "3V3") (class "Default")
      (node (ref "C12") (pin "2") (pinfunction "2_2") (pintype "passive"))
      (node (ref "C14") (pin "1") (pinfunction "1_1") (pintype "passive"))
      (node (ref "C19") (pin "1") (pinfunction "1_1") (pintype "passive"))
      (node (ref "C25") (pin "1") (pinfunction "1_1") (pintype "passive"))
      (node (ref "C33") (pin "1") (pinfunction "1_1") (pintype "passive"))
      (node (ref "C34") (pin "2") (pinfunction "2_2") (pintype "passive"))
      (node (ref "C6") (pin "1") (pinfunction "1_1") (pintype "passive"))
      (node (ref "C7") (pin "1") (pinfunction "1_1") (pintype "passive"))
      (node (ref "C8") (pin "1") (pinfunction "1_1") (pintype "passive"))
      (node (ref "IC3") (pin "10") (pinfunction "CSB_10") (pintype "bidirectional"))
      (node (ref "IC3") (pin "3") (pinfunction "VDDIO_3") (pintype "bidirectional"))
      (node (ref "IC3") (pin "7") (pinfunction "VDD_7") (pintype "bidirectional"))
      (node (ref "IC4") (pin "C2") (pinfunction "VDD_C2") (pintype "bidirectional"))
      (node (ref "IC9") (pin "E2") (pinfunction "VOUT_1_E2") (pintype "bidirectional"))
      (node (ref "IC9") (pin "E3") (pinfunction "VOUT_2_E3") (pintype "bidirectional"))
      (node (ref "J2") (pin "1") (pinfunction "1_1") (pintype "bidirectional"))
      (node (ref "Q1") (pin "2") (pinfunction "S_2") (pintype "bidirectional"))
      (node (ref "R17") (pin "1") (pinfunction "1_1") (pintype "bidirectional"))
      (node (ref "R18") (pin "1") (pinfunction "1_1") (pintype "bidirectional"))
      (node (ref "R5") (pin "2") (pinfunction "2_2") (pintype "bidirectional"))
      (node (ref "R7") (pin "2") (pinfunction "2_2") (pintype "bidirectional"))
      (node (ref "R8") (pin "2") (pinfunction "2_2") (pintype "bidirectional"))
      (node (ref "R_PWR_EPD") (pin "2") (pinfunction "2_2") (pintype "bidirectional"))
      (node (ref "TP_3.3V") (pin "TP") (pinfunction "TP_TP") (pintype "input"))
      (node (ref "TP_3V3") (pin "TP") (pinfunction "TP_TP") (pintype "input"))
      (node (ref "U1") (pin "P$A22") (pinfunction "VDD_P$A22") (pintype "power_in"))
      (node (ref "U1") (pin "P$AD14") (pinfunction "VDD_P$AD14") (pintype "power_in"))
      (node (ref "U1") (pin "P$AD23") (pinfunction "VDD_P$AD23") (pintype "power_in"))
      (node (ref "U1") (pin "P$B1") (pinfunction "VDD_P$B1") (pintype "power_in"))
      (node (ref "U1") (pin "P$W1") (pinfunction "VDD_P$W1") (pintype "power_in"))
      (node (ref "U1") (pin "P$Y2") (pinfunction "VDDH_P$Y2") (pintype "power_in"))
    )
    (net (code "2") (name "ALERT") (class "Default")
      (node (ref "U1") (pin "P$J24") (pinfunction "P0.10/NFC2_P$J24") (pintype "bidirectional"))
      (node (ref "U3") (pin "5") (pinfunction "~{ALERT}_5") (pintype "output"))
    )
    (net (code "3") (name "D+") (class "Default")
      (node (ref "D3") (pin "4") (pinfunction "I/O2_2_4") (pintype "bidirectional"))
      (node (ref "U1") (pin "P$AD6") (pinfunction "D+_P$AD6") (pintype "bidirectional"))
    )
    (net (code "4") (name "D-") (class "Default")
      (node (ref "D3") (pin "6") (pinfunction "I/O1_2_6") (pintype "bidirectional"))
      (node (ref "U1") (pin "P$AD4") (pinfunction "D-_P$AD4") (pintype "bidirectional"))
    )
    (net (code "5") (name "DN") (class "Default")
      (node (ref "D3") (pin "1") (pinfunction "I/O1_1_1") (pintype "bidirectional"))
      (node (ref "J4") (pin "A7") (pinfunction "DN1_A7") (pintype "bidirectional"))
      (node (ref "J4") (pin "B7") (pinfunction "DN2_B7") (pintype "bidirectional"))
    )
    (net (code "6") (name "DP") (class "Default")
      (node (ref "D3") (pin "3") (pinfunction "I/O2_1_3") (pintype "bidirectional"))
      (node (ref "J4") (pin "A6") (pinfunction "DP1_A6") (pintype "bidirectional"))
      (node (ref "J4") (pin "B6") (pinfunction "DP2_B6") (pintype "bidirectional"))
    )
    (net (code "7") (name "EPD_3V3") (class "Default")
      (node (ref "C1-EP_DR") (pin "1") (pinfunction "1_1") (pintype "passive"))
      (node (ref "EPD_C5") (pin "2") (pinfunction "2_2") (pintype "passive"))
      (node (ref "J1") (pin "15") (pinfunction "15_15") (pintype "bidirectional"))
      (node (ref "J1") (pin "16") (pinfunction "16_16") (pintype "bidirectional"))
      (node (ref "L5") (pin "2") (pinfunction "2_2") (pintype "passive"))
      (node (ref "Q1") (pin "3") (pinfunction "D_3") (pintype "bidirectional"))
    )
    (net (code "8") (name "EPD_BUSY") (class "Default")
      (node (ref "J1") (pin "9") (pinfunction "9_9") (pintype "bidirectional"))
      (node (ref "U1") (pin "P$AD12") (pinfunction "P0.17_P$AD12") (pintype "bidirectional"))
    )
    (net (code "9") (name "EPD_CS") (class "Default")
      (node (ref "J1") (pin "12") (pinfunction "12_12") (pintype "bidirectional"))
      (node (ref "U1") (pin "P$K2") (pinfunction "P0.05/AIN3_P$K2") (pintype "bidirectional"))
    )
    (net (code "10") (name "EPD_DC") (class "Default")
      (node (ref "J1") (pin "11") (pinfunction "11_11") (pintype "bidirectional"))
      (node (ref "U1") (pin "P$AD10") (pinfunction "P0.15_P$AD10") (pintype "bidirectional"))
    )
    (net (code "11") (name "EPD_RST") (class "Default")
      (node (ref "J1") (pin "10") (pinfunction "10_10") (pintype "bidirectional"))
      (node (ref "U1") (pin "P$AC11") (pinfunction "P0.16_P$AC11") (pintype "bidirectional"))
    )
    (net (code "12") (name "GDR") (class "Default")
      (node (ref "J1") (pin "2") (pinfunction "2_2") (pintype "bidirectional"))
      (node (ref "Q3") (pin "1") (pinfunction "G_1") (pintype "bidirectional"))
      (node (ref "R2_EP_DR") (pin "2") (pinfunction "2_2") (pintype "bidirectional"))
    )
    (net (code "13") (name "GND") (class "Default")
      (node (ref "C1") (pin "2") (pinfunction "2_2") (pintype "passive"))
      (node (ref "C1-EP_DR") (pin "2") (pinfunction "2_2") (pintype "passive"))
      (node (ref "C10") (pin "1") (pinfunction "1_1") (pintype "passive"))
      (node (ref "C11") (pin "1") (pinfunction "1_1") (pintype "passive"))
      (node (ref "C12") (pin "1") (pinfunction "1_1") (pintype "passive"))
      (node (ref "C13") (pin "1") (pinfunction "1_1") (pintype "passive"))
      (node (ref "C14") (pin "2") (pinfunction "2_2") (pintype "passive"))
      (node (ref "C15") (pin "2") (pinfunction "2_2") (pintype "passive"))
      (node (ref "C16") (pin "1") (pinfunction "1_1") (pintype "passive"))
      (node (ref "C17") (pin "1") (pinfunction "1_1") (pintype "passive"))
      (node (ref "C18") (pin "1") (pinfunction "1_1") (pintype "passive"))
      (node (ref "C19") (pin "2") (pinfunction "2_2") (pintype "passive"))
      (node (ref "C2") (pin "2") (pinfunction "2_2") (pintype "passive"))
      (node (ref "C20") (pin "2") (pinfunction "2_2") (pintype "passive"))
      (node (ref "C21") (pin "2") (pinfunction "2_2") (pintype "passive"))
      (node (ref "C22") (pin "1") (pinfunction "1_1") (pintype "passive"))
      (node (ref "C23") (pin "1") (pinfunction "1_1") (pintype "passive"))
      (node (ref "C24") (pin "1") (pinfunction "1_1") (pintype "passive"))
      (node (ref "C25") (pin "2") (pinfunction "2_2") (pintype "passive"))
      (node (ref "C27") (pin "1") (pinfunction "1_1") (pintype "passive"))
      (node (ref "C29") (pin "1") (pinfunction "1_1") (pintype "passive"))
      (node (ref "C3") (pin "2") (pinfunction "2_2") (pintype "passive"))
      (node (ref "C30") (pin "1") (pinfunction "1_1") (pintype "passive"))
      (node (ref "C31") (pin "1") (pinfunction "1_1") (pintype "passive"))
      (node (ref "C32") (pin "1") (pinfunction "1_1") (pintype "passive"))
      (node (ref "C33") (pin "2") (pinfunction "2_2") (pintype "passive"))
      (node (ref "C34") (pin "1") (pinfunction "1_1") (pintype "passive"))
      (node (ref "C37") (pin "1") (pinfunction "1_1") (pintype "passive"))
      (node (ref "C38") (pin "1") (pinfunction "1_1") (pintype "passive"))
      (node (ref "C39") (pin "2") (pinfunction "2_2") (pintype "passive"))
      (node (ref "C4") (pin "2") (pinfunction "2_2") (pintype "passive"))
      (node (ref "C42") (pin "2") (pinfunction "2_2") (pintype "passive"))
      (node (ref "C43") (pin "2") (pinfunction "2_2") (pintype "passive"))
      (node (ref "C5") (pin "2") (pinfunction "2_2") (pintype "passive"))
      (node (ref "C6") (pin "2") (pinfunction "2_2") (pintype "passive"))
      (node (ref "C7") (pin "2") (pinfunction "2_2") (pintype "passive"))
      (node (ref "C8") (pin "2") (pinfunction "2_2") (pintype "passive"))
      (node (ref "C9") (pin "2") (pinfunction "2_2") (pintype "passive"))
      (node (ref "D3") (pin "2") (pinfunction "GND_2") (pintype "bidirectional"))
      (node (ref "D4") (pin "1") (pinfunction "K_1") (pintype "bidirectional"))
      (node (ref "EPD_C1") (pin "1") (pinfunction "1_1") (pintype "passive"))
      (node (ref "EPD_C10") (pin "1") (pinfunction "1_1") (pintype "passive"))
      (node (ref "EPD_C11") (pin "1") (pinfunction "1_1") (pintype "passive"))
      (node (ref "EPD_C12") (pin "1") (pinfunction "1_1") (pintype "passive"))
      (node (ref "EPD_C2") (pin "1") (pinfunction "1_1") (pintype "passive"))
      (node (ref "EPD_C5") (pin "1") (pinfunction "1_1") (pintype "passive"))
      (node (ref "EPD_C6") (pin "1") (pinfunction "1_1") (pintype "passive"))
      (node (ref "EPD_C7") (pin "1") (pinfunction "1_1") (pintype "passive"))
      (node (ref "EPD_C8") (pin "1") (pinfunction "1_1") (pintype "passive"))
      (node (ref "EPD_C9") (pin "1") (pinfunction "1_1") (pintype "passive"))
      (node (ref "IC1") (pin "D2") (pinfunction "GND_D2") (pintype "bidirectional"))
      (node (ref "IC3") (pin "8") (pinfunction "GNDIO_8") (pintype "bidirectional"))
      (node (ref "IC3") (pin "9") (pinfunction "GND_9") (pintype "bidirectional"))
      (node (ref "IC4") (pin "B1") (pinfunction "IN/TRIG_B1") (pintype "bidirectional"))
      (node (ref "IC4") (pin "B3") (pinfunction "GND_B3") (pintype "bidirectional"))
      (node (ref "IC9") (pin "B1") (pinfunction "VSEL_B1") (pintype "bidirectional"))
      (node (ref "IC9") (pin "C1") (pinfunction "AGND_C1") (pintype "bidirectional"))
      (node (ref "IC9") (pin "C2") (pinfunction "PGND_1_C2") (pintype "bidirectional"))
      (node (ref "IC9") (pin "C3") (pinfunction "PGND_2_C3") (pintype "bidirectional"))
      (node (ref "J1") (pin "17") (pinfunction "17_17") (pintype "bidirectional"))
      (node (ref "J1") (pin "8") (pinfunction "8_8") (pintype "bidirectional"))
      (node (ref "J1") (pin "MP1") (pinfunction "MP1_MP1") (pintype "bidirectional"))
      (node (ref "J1") (pin "MP2") (pinfunction "MP2_MP2") (pintype "bidirectional"))
      (node (ref "J2") (pin "3") (pinfunction "3_3") (pintype "bidirectional"))
      (node (ref "J2") (pin "5") (pinfunction "5_5") (pintype "bidirectional"))
      (node (ref "J4") (pin "A12_B1") (pinfunction "GND_A12_B1") (pintype "power_in"))
      (node (ref "J4") (pin "A1_B12") (pinfunction "GND_A1_B12") (pintype "power_in"))
      (node (ref "J4") (pin "SH1") (pinfunction "SHIELD_SH1") (pintype "passive"))
      (node (ref "J4") (pin "SH2") (pinfunction "SHIELD_SH2") (pintype "passive"))
      (node (ref "J4") (pin "SH3") (pinfunction "SHIELD_SH3") (pintype "passive"))
      (node (ref "J4") (pin "SH4") (pinfunction "SHIELD_SH4") (pintype "passive"))
      (node (ref "R1_USB") (pin "1") (pinfunction "1_1") (pintype "bidirectional"))
      (node (ref "R2_EP_DR") (pin "1") (pinfunction "1_1") (pintype "bidirectional"))
      (node (ref "R2_USB") (pin "2") (pinfunction "2_2") (pintype "bidirectional"))
      (node (ref "R3") (pin "1") (pinfunction "1_1") (pintype "bidirectional"))
      (node (ref "R9") (pin "1") (pinfunction "1_1") (pintype "bidirectional"))
      (node (ref "R_TYPE_SEL") (pin "1") (pinfunction "1_1") (pintype "bidirectional"))
      (node (ref "SJ1") (pin "1") (pinfunction "1_1") (pintype "passive"))
      (node (ref "SW_DN") (pin "1") (pinfunction "1_1") (pintype "passive"))
      (node (ref "SW_ENT") (pin "1") (pinfunction "1_1") (pintype "passive"))
      (node (ref "SW_UP") (pin "1") (pinfunction "1_1") (pintype "passive"))
      (node (ref "TP_BAT_GND") (pin "TP") (pinfunction "TP_TP") (pintype "input"))
      (node (ref "TP_GND") (pin "TP") (pinfunction "TP_TP") (pintype "input"))
      (node (ref "U1") (pin "P$74") (pinfunction "VSS_PAD_P$74") (pintype "bidirectional"))
      (node (ref "U1") (pin "P$75") (pinfunction "VSS_PAD_P$75") (pintype "bidirectional"))
      (node (ref "U1") (pin "P$76") (pinfunction "VSS_PAD_P$76") (pintype "bidirectional"))
      (node (ref "U1") (pin "P$77") (pinfunction "VSS_PAD_P$77") (pintype "bidirectional"))
      (node (ref "U1") (pin "P$78") (pinfunction "VSS_PAD_P$78") (pintype "bidirectional"))
      (node (ref "U1") (pin "P$79") (pinfunction "VSS_PAD_P$79") (pintype "bidirectional"))
      (node (ref "U1") (pin "P$80") (pinfunction "VSS_PAD_P$80") (pintype "bidirectional"))
      (node (ref "U1") (pin "P$81") (pinfunction "VSS_PAD_P$81") (pintype "bidirectional"))
      (node (ref "U1") (pin "P$82") (pinfunction "VSS_PAD_P$82") (pintype "bidirectional"))
      (node (ref "U1") (pin "P$83") (pinfunction "VSS_PAD_P$83") (pintype "bidirectional"))
      (node (ref "U1") (pin "P$84") (pinfunction "VSS_PAD_P$84") (pintype "bidirectional"))
      (node (ref "U1") (pin "P$85") (pinfunction "VSS_PAD_P$85") (pintype "bidirectional"))
      (node (ref "U1") (pin "P$86") (pinfunction "VSS_PAD_P$86") (pintype "bidirectional"))
      (node (ref "U1") (pin "P$87") (pinfunction "VSS_PAD_P$87") (pintype "bidirectional"))
      (node (ref "U1") (pin "P$88") (pinfunction "VSS_PAD_P$88") (pintype "bidirectional"))
      (node (ref "U1") (pin "P$89") (pinfunction "VSS_PAD_P$89") (pintype "bidirectional"))
      (node (ref "U1") (pin "P$90") (pinfunction "VSS_PAD_P$90") (pintype "bidirectional"))
      (node (ref "U1") (pin "P$B7") (pinfunction "VSS_P$B7") (pintype "power_in"))
      (node (ref "U1") (pin "P$F23") (pinfunction "VSS_PA_P$F23") (pintype "bidirectional"))
      (node (ref "U3") (pin "1") (pinfunction "CTG_1") (pintype "power_in"))
      (node (ref "U3") (pin "4") (pinfunction "GND_4") (pintype "power_in"))
      (node (ref "U3") (pin "6") (pinfunction "QSTRT_6") (pintype "input"))
      (node (ref "U3") (pin "9") (pinfunction "EP_9") (pintype "power_in"))
      (node (ref "X1") (pin "2") (pinfunction "2_2") (pintype "passive"))
      (node (ref "X1") (pin "4") (pinfunction "4_4") (pintype "passive"))
    )
    (net (code "14") (name "HAPTIC_EN") (class "Default")
      (node (ref "IC4") (pin "A1") (pinfunction "EN_A1") (pintype "bidirectional"))
      (node (ref "U1") (pin "P$U1") (pinfunction "P0.12_P$U1") (pintype "bidirectional"))
    )
    (net (code "15") (name "IMU_INT1") (class "Default")
      (node (ref "IC3") (pin "5") (pinfunction "INT1_5") (pintype "bidirectional"))
      (node (ref "U1") (pin "P$N1") (pinfunction "P0.08_P$N1") (pintype "bidirectional"))
    )
    (net (code "16") (name "IMU_INT2") (class "Default")
      (node (ref "IC3") (pin "6") (pinfunction "INT2_6") (pintype "bidirectional"))
      (node (ref "U1") (pin "P$P2") (pinfunction "P1.08_P$P2") (pintype "bidirectional"))
    )
    (net (code "17") (name "LX1") (class "Default")
      (node (ref "IC9") (pin "B2") (pinfunction "SW1_1_B2") (pintype "bidirectional"))
      (node (ref "IC9") (pin "B3") (pinfunction "SW1_2_B3") (pintype "bidirectional"))
      (node (ref "L7") (pin "1") (pinfunction "1_1") (pintype "bidirectional"))
    )
    (net (code "18") (name "LX2") (class "Default")
      (node (ref "IC9") (pin "D2") (pinfunction "SW2_1_D2") (pintype "bidirectional"))
      (node (ref "IC9") (pin "D3") (pinfunction "SW2_2_D3") (pintype "bidirectional"))
      (node (ref "L7") (pin "2") (pinfunction "2_2") (pintype "bidirectional"))
    )
    (net (code "19") (name "MOSI") (class "Default")
      (node (ref "J1") (pin "14") (pinfunction "14_14") (pintype "bidirectional"))
      (node (ref "U1") (pin "P$B13") (pinfunction "P0.03/AIN1_P$B13") (pintype "bidirectional"))
    )
    (net (code "20") (name "Net-(ANT1-FEED)") (class "Default")
      (node (ref "ANT1") (pin "1") (pinfunction "FEED_1") (pintype "input"))
      (node (ref "C22") (pin "2") (pinfunction "2_2") (pintype "passive"))
      (node (ref "C4") (pin "1") (pinfunction "1_1") (pintype "passive"))
      (node (ref "L1") (pin "2") (pinfunction "2_2") (pintype "passive"))
    )
    (net (code "21") (name "Net-(D2-K)") (class "Default")
      (node (ref "C2-EP_DR") (pin "1") (pinfunction "1_1") (pintype "passive"))
      (node (ref "D2") (pin "1") (pinfunction "K_1") (pintype "bidirectional"))
      (node (ref "D4") (pin "2") (pinfunction "A_2") (pintype "bidirectional"))
    )
    (net (code "22") (name "Net-(D5-A)") (class "Default")
      (node (ref "C2-EP_DR") (pin "2") (pinfunction "2_2") (pintype "passive"))
      (node (ref "D5") (pin "2") (pinfunction "A_2") (pintype "bidirectional"))
      (node (ref "L5") (pin "1") (pinfunction "1_1") (pintype "passive"))
      (node (ref "Q3") (pin "3") (pinfunction "D_3") (pintype "bidirectional"))
    )
    (net (code "23") (name "Net-(EPD_C1-Pad2)") (class "Default")
      (node (ref "EPD_C1") (pin "2") (pinfunction "2_2") (pintype "passive"))
      (node (ref "J1") (pin "5") (pinfunction "5_5") (pintype "bidirectional"))
    )
    (net (code "24") (name "Net-(EPD_C2-Pad2)") (class "Default")
      (node (ref "EPD_C2") (pin "2") (pinfunction "2_2") (pintype "passive"))
      (node (ref "J1") (pin "4") (pinfunction "4_4") (pintype "bidirectional"))
    )
    (net (code "25") (name "Net-(EPD_C6-Pad2)") (class "Default")
      (node (ref "EPD_C6") (pin "2") (pinfunction "2_2") (pintype "passive"))
      (node (ref "J1") (pin "18") (pinfunction "18_18") (pintype "bidirectional"))
    )
    (net (code "26") (name "Net-(EPD_C7-Pad2)") (class "Default")
      (node (ref "EPD_C7") (pin "2") (pinfunction "2_2") (pintype "passive"))
      (node (ref "J1") (pin "19") (pinfunction "19_19") (pintype "bidirectional"))
    )
    (net (code "27") (name "Net-(EPD_C8-Pad2)") (class "Default")
      (node (ref "EPD_C8") (pin "2") (pinfunction "2_2") (pintype "passive"))
      (node (ref "J1") (pin "20") (pinfunction "20_20") (pintype "bidirectional"))
    )
    (net (code "28") (name "Net-(EPD_C10-Pad2)") (class "Default")
      (node (ref "EPD_C10") (pin "2") (pinfunction "2_2") (pintype "passive"))
      (node (ref "J1") (pin "22") (pinfunction "22_22") (pintype "bidirectional"))
    )
    (net (code "29") (name "Net-(EPD_C12-Pad2)") (class "Default")
      (node (ref "EPD_C12") (pin "2") (pinfunction "2_2") (pintype "passive"))
      (node (ref "J1") (pin "24") (pinfunction "24_24") (pintype "bidirectional"))
    )
    (net (code "30") (name "Net-(IC1-TS{slash}MR)") (class "Default")
      (node (ref "IC1") (pin "D1") (pinfunction "TS/MR_D1") (pintype "bidirectional"))
      (node (ref "R9") (pin "2") (pinfunction "2_2") (pintype "bidirectional"))
    )
    (net (code "31") (name "Net-(IC3-SDO)") (class "Default")
      (node (ref "IC3") (pin "1") (pinfunction "SDO_1") (pintype "bidirectional"))
      (node (ref "R3") (pin "2") (pinfunction "2_2") (pintype "bidirectional"))
    )
    (net (code "32") (name "Net-(IC4-REG)") (class "Default")
      (node (ref "C32") (pin "2") (pinfunction "2_2") (pintype "passive"))
      (node (ref "IC4") (pin "A2") (pinfunction "REG_A2") (pintype "bidirectional"))
    )
    (net (code "33") (name "Net-(IC9-SCL)") (class "Default")
      (node (ref "IC9") (pin "D1") (pinfunction "SCL_D1") (pintype "bidirectional"))
      (node (ref "R4") (pin "2") (pinfunction "2_2") (pintype "bidirectional"))
    )
    (net (code "34") (name "Net-(IC9-SDA)") (class "Default")
      (node (ref "IC9") (pin "E1") (pinfunction "SDA_E1") (pintype "bidirectional"))
      (node (ref "R2") (pin "2") (pinfunction "2_2") (pintype "bidirectional"))
    )
    (net (code "35") (name "Net-(J4-CC1)") (class "Default")
      (node (ref "J4") (pin "A5") (pinfunction "CC1_A5") (pintype "bidirectional"))
      (node (ref "R1_USB") (pin "2") (pinfunction "2_2") (pintype "bidirectional"))
    )
    (net (code "36") (name "Net-(J4-CC2)") (class "Default")
      (node (ref "J4") (pin "B5") (pinfunction "CC2_B5") (pintype "bidirectional"))
      (node (ref "R2_USB") (pin "1") (pinfunction "1_1") (pintype "bidirectional"))
    )
    (net (code "37") (name "Net-(L2-Pad2)") (class "Default")
      (node (ref "L2") (pin "2") (pinfunction "2_2") (pintype "passive"))
      (node (ref "L3") (pin "1") (pinfunction "1_1") (pintype "passive"))
    )
    (net (code "38") (name "Net-(R1_EP_DR-Pad1)") (class "Default")
      (node (ref "R1_EP_DR") (pin "1") (pinfunction "1_1") (pintype "bidirectional"))
      (node (ref "R_TYPE_SEL") (pin "2") (pinfunction "2_2") (pintype "bidirectional"))
      (node (ref "SJ1") (pin "2") (pinfunction "2_2") (pintype "passive"))
    )
    (net (code "39") (name "Net-(U1-ANT)") (class "Default")
      (node (ref "C3") (pin "1") (pinfunction "1_1") (pintype "passive"))
      (node (ref "L1") (pin "1") (pinfunction "1_1") (pintype "passive"))
      (node (ref "U1") (pin "P$H23") (pinfunction "ANT_P$H23") (pintype "bidirectional"))
    )
    (net (code "40") (name "Net-(U1-DCC)") (class "Default")
      (node (ref "L2") (pin "1") (pinfunction "1_1") (pintype "passive"))
      (node (ref "U1") (pin "P$B3") (pinfunction "DCC_P$B3") (pintype "output"))
    )
    (net (code "41") (name "Net-(U1-DEC1)") (class "Default")
      (node (ref "C5") (pin "1") (pinfunction "1_1") (pintype "passive"))
      (node (ref "U1") (pin "P$C1") (pinfunction "DEC1_P$C1") (pintype "power_in"))
    )
    (net (code "42") (name "Net-(U1-DEC2)") (class "Default")
      (node (ref "C13") (pin "2") (pinfunction "2_2") (pintype "passive"))
      (node (ref "U1") (pin "P$A18") (pinfunction "DEC2_P$A18") (pintype "bidirectional"))
    )
    (net (code "43") (name "Net-(U1-DEC3)") (class "Default")
      (node (ref "C11") (pin "2") (pinfunction "2_2") (pintype "passive"))
      (node (ref "U1") (pin "P$D23") (pinfunction "DEC3_P$D23") (pintype "bidirectional"))
    )
    (net (code "44") (name "Net-(U1-DEC3V3)") (class "Default")
      (node (ref "C20") (pin "1") (pinfunction "1_1") (pintype "passive"))
      (node (ref "U1") (pin "P$AC5") (pinfunction "DEC3V3_P$AC5") (pintype "bidirectional"))
    )
    (net (code "45") (name "Net-(U1-DEC4)") (class "Default")
      (node (ref "C10") (pin "2") (pinfunction "2_2") (pintype "passive"))
      (node (ref "C15") (pin "1") (pinfunction "1_1") (pintype "passive"))
      (node (ref "C16") (pin "2") (pinfunction "2_2") (pintype "passive"))
      (node (ref "L3") (pin "2") (pinfunction "2_2") (pintype "passive"))
      (node (ref "U1") (pin "P$B5") (pinfunction "DEC4_P$B5") (pintype "power_in"))
      (node (ref "U1") (pin "P$E24") (pinfunction "DEC6_P$E24") (pintype "bidirectional"))
    )
    (net (code "46") (name "Net-(U1-DEC5)") (class "Default")
      (node (ref "C9") (pin "1") (pinfunction "1_1") (pintype "passive"))
      (node (ref "U1") (pin "P$N24") (pinfunction "DEC5_P$N24") (pintype "bidirectional"))
    )
    (net (code "47") (name "Net-(U1-P0.00{slash}XL1)") (class "Default")
      (node (ref "C17") (pin "2") (pinfunction "2_2") (pintype "passive"))
      (node (ref "U1") (pin "P$D2") (pinfunction "P0.00/XL1_P$D2") (pintype "bidirectional"))
      (node (ref "X2") (pin "1") (pinfunction "1_1") (pintype "passive"))
    )
    (net (code "48") (name "Net-(U1-P0.01{slash}XL2)") (class "Default")
      (node (ref "C18") (pin "2") (pinfunction "2_2") (pintype "passive"))
      (node (ref "U1") (pin "P$F2") (pinfunction "P0.01/XL2_P$F2") (pintype "bidirectional"))
      (node (ref "X2") (pin "2") (pinfunction "2_2") (pintype "passive"))
    )
    (net (code "49") (name "Net-(U1-XC1)") (class "Default")
      (node (ref "C1") (pin "1") (pinfunction "1_1") (pintype "passive"))
      (node (ref "U1") (pin "P$B24") (pinfunction "XC1_P$B24") (pintype "input"))
      (node (ref "X1") (pin "1") (pinfunction "1_1") (pintype "passive"))
    )
    (net (code "50") (name "Net-(U1-XC2)") (class "Default")
      (node (ref "C2") (pin "1") (pinfunction "1_1") (pintype "passive"))
      (node (ref "U1") (pin "P$A23") (pinfunction "XC2_P$A23") (pintype "output"))
      (node (ref "X1") (pin "3") (pinfunction "3_3") (pintype "passive"))
    )
    (net (code "51") (name "OUT+") (class "Default")
      (node (ref "IC4") (pin "A3") (pinfunction "OUT+_A3") (pintype "bidirectional"))
      (node (ref "TP_OP") (pin "TP") (pinfunction "TP_TP") (pintype "input"))
    )
    (net (code "52") (name "OUT-") (class "Default")
      (node (ref "IC4") (pin "C3") (pinfunction "OUT-_C3") (pintype "bidirectional"))
      (node (ref "TP_ON") (pin "TP") (pinfunction "TP_TP") (pintype "input"))
    )
    (net (code "53") (name "P0.04") (class "Default")
      (node (ref "U1") (pin "P$J1") (pinfunction "P0.04/AIN2_P$J1") (pintype "bidirectional"))
    )
    (net (code "54") (name "P0.09") (class "Default")
      (node (ref "U1") (pin "P$L24") (pinfunction "P0.09/NFC1_P$L24") (pintype "bidirectional"))
    )
    (net (code "55") (name "P0.13") (class "Default")
      (node (ref "C30") (pin "2") (pinfunction "2_2") (pintype "passive"))
      (node (ref "R5") (pin "1") (pinfunction "1_1") (pintype "bidirectional"))
      (node (ref "SW_UP") (pin "2") (pinfunction "2_2") (pintype "passive"))
      (node (ref "U1") (pin "P$AD8") (pinfunction "P0.13_P$AD8") (pintype "bidirectional"))
    )
    (net (code "56") (name "P0.14") (class "Default")
      (node (ref "C31") (pin "2") (pinfunction "2_2") (pintype "passive"))
      (node (ref "R8") (pin "1") (pinfunction "1_1") (pintype "bidirectional"))
      (node (ref "SW_ENT") (pin "2") (pinfunction "2_2") (pintype "passive"))
      (node (ref "U1") (pin "P$AC9") (pinfunction "P0.14_P$AC9") (pintype "bidirectional"))
    )
    (net (code "57") (name "P0.19") (class "Default")
      (node (ref "U1") (pin "P$AC15") (pinfunction "P0.19_P$AC15") (pintype "bidirectional"))
    )
    (net (code "58") (name "P0.20") (class "Default")
      (node (ref "U1") (pin "P$AD16") (pinfunction "P0.20_P$AD16") (pintype "bidirectional"))
    )
    (net (code "59") (name "P0.21") (class "Default")
      (node (ref "U1") (pin "P$AC17") (pinfunction "P0.21_P$AC17") (pintype "bidirectional"))
    )
    (net (code "60") (name "P0.22") (class "Default")
      (node (ref "U1") (pin "P$AD18") (pinfunction "P0.22_P$AD18") (pintype "bidirectional"))
    )
    (net (code "61") (name "P0.23") (class "Default")
      (node (ref "U1") (pin "P$AC19") (pinfunction "P0.23_P$AC19") (pintype "bidirectional"))
    )
    (net (code "62") (name "P0.24") (class "Default")
      (node (ref "U1") (pin "P$AD20") (pinfunction "P0.24_P$AD20") (pintype "bidirectional"))
    )
    (net (code "63") (name "P0.25") (class "Default")
      (node (ref "U1") (pin "P$AC21") (pinfunction "P0.25_P$AC21") (pintype "bidirectional"))
    )
    (net (code "64") (name "P0.26") (class "Default")
      (node (ref "U1") (pin "P$G1") (pinfunction "P0.26_P$G1") (pintype "bidirectional"))
    )
    (net (code "65") (name "P0.27") (class "Default")
      (node (ref "U1") (pin "P$H2") (pinfunction "P0.27_P$H2") (pintype "bidirectional"))
    )
    (net (code "66") (name "P0.28") (class "Default")
      (node (ref "U1") (pin "P$B11") (pinfunction "P0.28/AIN4_P$B11") (pintype "bidirectional"))
    )
    (net (code "67") (name "P0.29") (class "Default")
      (node (ref "U1") (pin "P$A10") (pinfunction "P0.29/AIN5_P$A10") (pintype "bidirectional"))
    )
    (net (code "68") (name "P0.30") (class "Default")
      (node (ref "U1") (pin "P$B9") (pinfunction "P0.30/AIN6_P$B9") (pintype "bidirectional"))
    )
    (net (code "69") (name "P0.31") (class "Default")
      (node (ref "U1") (pin "P$A8") (pinfunction "P0.31/AIN7_P$A8") (pintype "bidirectional"))
    )
    (net (code "70") (name "P1.01") (class "Default")
      (node (ref "Q1") (pin "1") (pinfunction "G_1") (pintype "bidirectional"))
      (node (ref "R_PWR_EPD") (pin "1") (pinfunction "1_1") (pintype "bidirectional"))
      (node (ref "U1") (pin "P$Y23") (pinfunction "P1.01_P$Y23") (pintype "bidirectional"))
    )
    (net (code "71") (name "P1.02") (class "Default")
      (node (ref "C29") (pin "2") (pinfunction "2_2") (pintype "passive"))
      (node (ref "R7") (pin "1") (pinfunction "1_1") (pintype "bidirectional"))
      (node (ref "SW_DN") (pin "2") (pinfunction "2_2") (pintype "passive"))
      (node (ref "U1") (pin "P$W24") (pinfunction "P1.02_P$W24") (pintype "bidirectional"))
    )
    (net (code "72") (name "P1.03") (class "Default")
      (node (ref "U1") (pin "P$V23") (pinfunction "P1.03_P$V23") (pintype "bidirectional"))
    )
    (net (code "73") (name "P1.04") (class "Default")
      (node (ref "U1") (pin "P$U24") (pinfunction "P1.04_P$U24") (pintype "bidirectional"))
    )
    (net (code "74") (name "P1.05") (class "Default")
      (node (ref "U1") (pin "P$T23") (pinfunction "P1.05_P$T23") (pintype "bidirectional"))
    )
    (net (code "75") (name "P1.06") (class "Default")
      (node (ref "U1") (pin "P$R24") (pinfunction "P1.06_P$R24") (pintype "bidirectional"))
    )
    (net (code "76") (name "P1.07") (class "Default")
      (node (ref "U1") (pin "P$P23") (pinfunction "P1.07_P$P23") (pintype "bidirectional"))
    )
    (net (code "77") (name "P1.09") (class "Default")
      (node (ref "U1") (pin "P$R1") (pinfunction "P1.09_P$R1") (pintype "bidirectional"))
    )
    (net (code "78") (name "P1.10") (class "Default")
      (node (ref "U1") (pin "P$A20") (pinfunction "P1.10_P$A20") (pintype "bidirectional"))
    )
    (net (code "79") (name "P1.11") (class "Default")
      (node (ref "U1") (pin "P$B19") (pinfunction "P1.11_P$B19") (pintype "bidirectional"))
    )
    (net (code "80") (name "P1.12") (class "Default")
      (node (ref "U1") (pin "P$B17") (pinfunction "P1.12_P$B17") (pintype "bidirectional"))
    )
    (net (code "81") (name "P1.13") (class "Default")
      (node (ref "U1") (pin "P$A16") (pinfunction "P1.13_P$A16") (pintype "bidirectional"))
    )
    (net (code "82") (name "P1.14") (class "Default")
      (node (ref "U1") (pin "P$B15") (pinfunction "P1.14_P$B15") (pintype "bidirectional"))
    )
    (net (code "83") (name "P1.15") (class "Default")
      (node (ref "U1") (pin "P$A14") (pinfunction "P1.15_P$A14") (pintype "bidirectional"))
    )
    (net (code "84") (name "PMIC_INT") (class "Default")
      (node (ref "IC1") (pin "A1") (pinfunction "~{INT}_A1") (pintype "bidirectional"))
      (node (ref "U1") (pin "P$T2") (pinfunction "P0.11_P$T2") (pintype "bidirectional"))
    )
    (net (code "85") (name "PREVGH") (class "Default")
      (node (ref "D5") (pin "1") (pinfunction "K_1") (pintype "bidirectional"))
      (node (ref "EPD_C9") (pin "2") (pinfunction "2_2") (pintype "passive"))
      (node (ref "J1") (pin "21") (pinfunction "21_21") (pintype "bidirectional"))
    )
    (net (code "86") (name "PREVGL") (class "Default")
      (node (ref "D2") (pin "2") (pinfunction "A_2") (pintype "bidirectional"))
      (node (ref "EPD_C11") (pin "2") (pinfunction "2_2") (pintype "passive"))
      (node (ref "J1") (pin "23") (pinfunction "23_23") (pintype "bidirectional"))
    )
    (net (code "87") (name "RESE") (class "Default")
      (node (ref "J1") (pin "3") (pinfunction "3_3") (pintype "bidirectional"))
      (node (ref "Q3") (pin "2") (pinfunction "S_2") (pintype "bidirectional"))
      (node (ref "R1_EP_DR") (pin "2") (pinfunction "2_2") (pintype "bidirectional"))
    )
    (net (code "88") (name "RESET") (class "Default")
      (node (ref "J2") (pin "6") (pinfunction "6_6") (pintype "bidirectional"))
      (node (ref "TP_RESET") (pin "TP") (pinfunction "TP_TP") (pintype "input"))
      (node (ref "U1") (pin "P$AC13") (pinfunction "P0.18/RESET_P$AC13") (pintype "bidirectional"))
    )
    (net (code "89") (name "SCK") (class "Default")
      (node (ref "J1") (pin "13") (pinfunction "13_13") (pintype "bidirectional"))
      (node (ref "U1") (pin "P$A12") (pinfunction "P0.02/AIN0_P$A12") (pintype "bidirectional"))
    )
    (net (code "90") (name "SCL") (class "Default")
      (node (ref "IC1") (pin "B1") (pinfunction "SCL_B1") (pintype "bidirectional"))
      (node (ref "IC3") (pin "12") (pinfunction "SCX_12") (pintype "bidirectional"))
      (node (ref "IC4") (pin "C1") (pinfunction "SCL_C1") (pintype "bidirectional"))
      (node (ref "R17") (pin "2") (pinfunction "2_2") (pintype "bidirectional"))
      (node (ref "R4") (pin "1") (pinfunction "1_1") (pintype "bidirectional"))
      (node (ref "TP_SCL") (pin "TP") (pinfunction "TP_TP") (pintype "input"))
      (node (ref "U1") (pin "P$M2") (pinfunction "P0.07_P$M2") (pintype "bidirectional"))
      (node (ref "U3") (pin "7") (pinfunction "SCL_7") (pintype "input"))
    )
    (net (code "91") (name "SDA") (class "Default")
      (node (ref "IC1") (pin "C1") (pinfunction "SDA_C1") (pintype "bidirectional"))
      (node (ref "IC3") (pin "2") (pinfunction "SDX_2") (pintype "bidirectional"))
      (node (ref "IC4") (pin "B2") (pinfunction "SDA_B2") (pintype "bidirectional"))
      (node (ref "R18") (pin "2") (pinfunction "2_2") (pintype "bidirectional"))
      (node (ref "R2") (pin "1") (pinfunction "1_1") (pintype "bidirectional"))
      (node (ref "TP_SDA") (pin "TP") (pinfunction "TP_TP") (pintype "input"))
      (node (ref "U1") (pin "P$L1") (pinfunction "P0.06_P$L1") (pintype "bidirectional"))
      (node (ref "U3") (pin "8") (pinfunction "SDA_8") (pintype "bidirectional"))
    )
    (net (code "92") (name "SWDCLK") (class "Default")
      (node (ref "J2") (pin "4") (pinfunction "4_4") (pintype "bidirectional"))
      (node (ref "TP_SWDCLK") (pin "TP") (pinfunction "TP_TP") (pintype "input"))
      (node (ref "U1") (pin "P$AA24") (pinfunction "SWDCLK_P$AA24") (pintype "input"))
    )
    (net (code "93") (name "SWDIO") (class "Default")
      (node (ref "J2") (pin "2") (pinfunction "2_2") (pintype "bidirectional"))
      (node (ref "TP_SWDIO") (pin "TP") (pinfunction "TP_TP") (pintype "input"))
      (node (ref "U1") (pin "P$AC24") (pinfunction "SWDIO_P$AC24") (pintype "bidirectional"))
    )
    (net (code "94") (name "SWO") (class "Default")
      (node (ref "TP_SWO") (pin "TP") (pinfunction "TP_TP") (pintype "input"))
      (node (ref "U1") (pin "P$AD22") (pinfunction "P1.00_P$AD22") (pintype "bidirectional"))
    )
    (net (code "95") (name "VBAT") (class "Default")
      (node (ref "C27") (pin "2") (pinfunction "2_2") (pintype "passive"))
      (node (ref "C37") (pin "2") (pinfunction "2_2") (pintype "passive"))
      (node (ref "IC1") (pin "C2") (pinfunction "BAT_C2") (pintype "bidirectional"))
      (node (ref "TP_VBAT") (pin "TP") (pinfunction "TP_TP") (pintype "input"))
      (node (ref "U3") (pin "2") (pinfunction "CELL_2") (pintype "power_in"))
      (node (ref "U3") (pin "3") (pinfunction "VDD_3") (pintype "power_in"))
    )
    (net (code "96") (name "VBUS") (class "Default")
      (node (ref "C21") (pin "1") (pinfunction "1_1") (pintype "passive"))
      (node (ref "C38") (pin "2") (pinfunction "2_2") (pintype "passive"))
      (node (ref "C42") (pin "1") (pinfunction "1_1") (pintype "passive"))
      (node (ref "C43") (pin "1") (pinfunction "1_1") (pintype "passive"))
      (node (ref "D3") (pin "5") (pinfunction "VBUS_5") (pintype "bidirectional"))
      (node (ref "IC1") (pin "A2") (pinfunction "IN_A2") (pintype "bidirectional"))
      (node (ref "J4") (pin "A4_B9") (pinfunction "VBUS_A4_B9") (pintype "power_in"))
      (node (ref "J4") (pin "A9_B4") (pinfunction "VBUS_A9_B4") (pintype "power_in"))
      (node (ref "U1") (pin "P$AD2") (pinfunction "VBUS_P$AD2") (pintype "power_in"))
    )
    (net (code "97") (name "VREG") (class "Default")
      (node (ref "C23") (pin "2") (pinfunction "2_2") (pintype "passive"))
      (node (ref "C24") (pin "2") (pinfunction "2_2") (pintype "passive"))
      (node (ref "C39") (pin "1") (pinfunction "1_1") (pintype "passive"))
      (node (ref "IC1") (pin "B2") (pinfunction "SYS_B2") (pintype "bidirectional"))
      (node (ref "IC9") (pin "A1") (pinfunction "EN_A1") (pintype "bidirectional"))
      (node (ref "IC9") (pin "A2") (pinfunction "VIN_1_A2") (pintype "bidirectional"))
      (node (ref "IC9") (pin "A3") (pinfunction "VIN_2_A3") (pintype "bidirectional"))
      (node (ref "TP_VREG") (pin "TP") (pinfunction "TP_TP") (pintype "input"))
    )
    (net (code "98") (name "unconnected-(ANT1-NC-Pad2)") (class "Default")
      (node (ref "ANT1") (pin "2") (pinfunction "NC_2") (pintype "no_connect"))
    )
    (net (code "99") (name "unconnected-(IC3-ASCL-Pad11)") (class "Default")
      (node (ref "IC3") (pin "11") (pinfunction "ASCL_11") (pintype "bidirectional"))
    )
    (net (code "100") (name "unconnected-(IC3-ASDA-Pad4)") (class "Default")
      (node (ref "IC3") (pin "4") (pinfunction "ASDA_4") (pintype "bidirectional"))
    )
    (net (code "101") (name "unconnected-(J1-Pad1)") (class "Default")
      (node (ref "J1") (pin "1") (pinfunction "1_1") (pintype "bidirectional"))
    )
    (net (code "102") (name "unconnected-(J1-Pad6)") (class "Default")
      (node (ref "J1") (pin "6") (pinfunction "6_6") (pintype "bidirectional"))
    )
    (net (code "103") (name "unconnected-(J1-Pad7)") (class "Default")
      (node (ref "J1") (pin "7") (pinfunction "7_7") (pintype "bidirectional"))
    )
    (net (code "104") (name "unconnected-(J4-SBU1-PadA8)") (class "Default")
      (node (ref "J4") (pin "A8") (pinfunction "SBU1_A8") (pintype "bidirectional"))
    )
    (net (code "105") (name "unconnected-(J4-SBU2-PadB8)") (class "Default")
      (node (ref "J4") (pin "B8") (pinfunction "SBU2_B8") (pintype "bidirectional"))
    )
    (net (code "106") (name "unconnected-(U1-DCCH-PadP$AB2)") (class "Default")
      (node (ref "U1") (pin "P$AB2") (pinfunction "DCCH_P$AB2") (pintype "bidirectional"))
    )
  )
)
